# 6-gsm_ctrl.net
KiCad netlist of a schematic drawn in Altium Designer
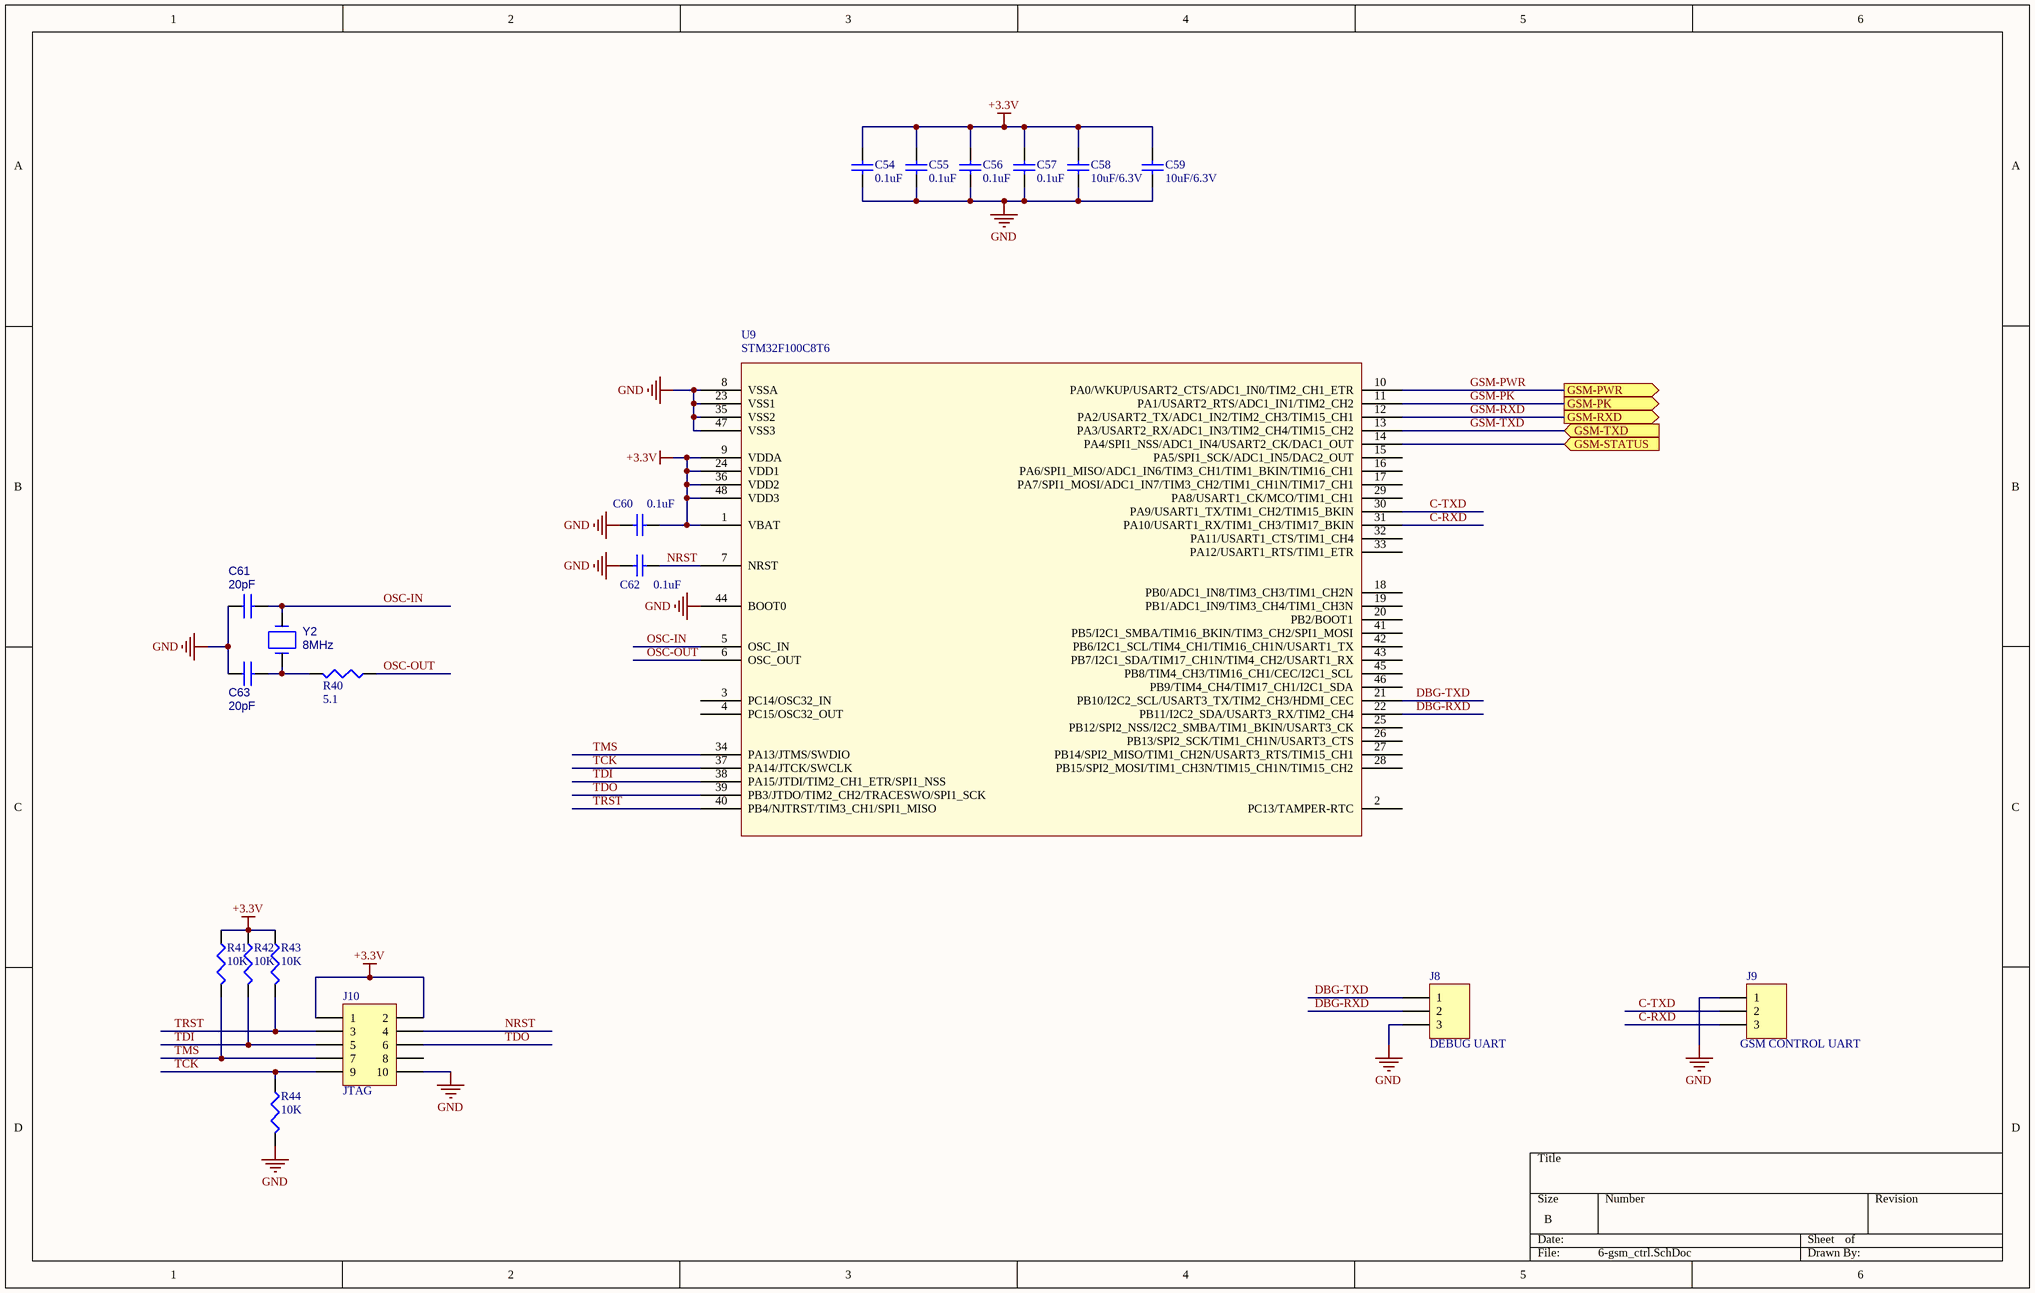
[diagram p0: 6-gsm_ctrl.SchDoc]

(export (version "E")
  (design (tool "Eeschema 10.0.6"))
  (components
    (comp (ref "C54")
      (value "0.1uF")
      (footprint "0603")
      (description "Capacitor")
      (fields (field (name "PUBLISHER") "Altium Limited"))
      (libsource (lib "Miscellaneous Devices") (part "Cap"))
    )
    (comp (ref "C55")
      (value "0.1uF")
      (footprint "0603")
      (description "Capacitor")
      (fields (field (name "PUBLISHER") "Altium Limited"))
      (libsource (lib "Miscellaneous Devices") (part "Cap"))
    )
    (comp (ref "C56")
      (value "0.1uF")
      (footprint "0603")
      (description "Capacitor")
      (fields (field (name "PUBLISHER") "Altium Limited"))
      (libsource (lib "Miscellaneous Devices") (part "Cap"))
    )
    (comp (ref "C57")
      (value "0.1uF")
      (footprint "0603")
      (description "Capacitor")
      (fields (field (name "PUBLISHER") "Altium Limited"))
      (libsource (lib "Miscellaneous Devices") (part "Cap"))
    )
    (comp (ref "C58")
      (value "10uF/6.3V")
      (footprint "0805")
      (description "Capacitor")
      (fields (field (name "PUBLISHER") "Altium Limited"))
      (libsource (lib "Miscellaneous Devices") (part "Cap"))
    )
    (comp (ref "C59")
      (value "10uF/6.3V")
      (footprint "0805")
      (description "Capacitor")
      (fields (field (name "PUBLISHER") "Altium Limited"))
      (libsource (lib "Miscellaneous Devices") (part "Cap"))
    )
    (comp (ref "C60")
      (value "0.1uF")
      (footprint "0603")
      (description "Capacitor")
      (fields (field (name "PUBLISHER") "Altium Limited"))
      (libsource (lib "Miscellaneous Devices") (part "Cap"))
    )
    (comp (ref "C61") (value "20pF") (libsource (lib "*") (part "CAP_Dup1")))
    (comp (ref "C62")
      (value "0.1uF")
      (footprint "0603")
      (description "Capacitor")
      (fields (field (name "PUBLISHER") "Altium Limited"))
      (libsource (lib "Miscellaneous Devices") (part "Cap"))
    )
    (comp (ref "C63") (value "20pF") (libsource (lib "*") (part "CAP_Dup1")))
    (comp (ref "J8")
      (value "DEBUG UART")
      (footprint "HDR1X3")
      (description "Header, 3-Pin")
      (fields (field (name "PUBLISHER") "Altium Limited"))
      (libsource (lib "Miscellaneous Connectors") (part "Header 3"))
    )
    (comp (ref "J9")
      (value "GSM CONTROL UART")
      (footprint "CONN-3P")
      (description "Header, 3-Pin")
      (fields (field (name "PUBLISHER") "Altium Limited"))
      (libsource (lib "Miscellaneous Connectors") (part "Header 3"))
    )
    (comp (ref "J10")
      (value "JTAG")
      (footprint "HDR2X5")
      (description "Header, 5-Pin, Dual row")
      (fields (field (name "PUBLISHER") "Altium Limited"))
      (libsource (lib "Miscellaneous Connectors") (part "Header 5X2"))
    )
    (comp (ref "R40")
      (value "5.1")
      (footprint "0603")
      (description "Resistor")
      (fields (field (name "PUBLISHER") "Altium Limited"))
      (libsource (lib "Miscellaneous Devices") (part "Res3"))
    )
    (comp (ref "R41")
      (value "10K")
      (footprint "0603")
      (description "Resistor")
      (fields (field (name "PUBLISHER") "Altium Limited"))
      (libsource (lib "Miscellaneous Devices") (part "Res3"))
    )
    (comp (ref "R42")
      (value "10K")
      (footprint "0603")
      (description "Resistor")
      (fields (field (name "PUBLISHER") "Altium Limited"))
      (libsource (lib "Miscellaneous Devices") (part "Res3"))
    )
    (comp (ref "R43")
      (value "10K")
      (footprint "0603")
      (description "Resistor")
      (fields (field (name "PUBLISHER") "Altium Limited"))
      (libsource (lib "Miscellaneous Devices") (part "Res3"))
    )
    (comp (ref "R44")
      (value "10K")
      (footprint "0603")
      (description "Resistor")
      (fields (field (name "PUBLISHER") "Altium Limited"))
      (libsource (lib "Miscellaneous Devices") (part "Res3"))
    )
    (comp (ref "U9")
      (value "STM32F100C8T6")
      (footprint "LQFP48")
      (libsource (lib "Schlib") (part "STM32F100XX-LQFP48"))
    )
    (comp (ref "Y2") (value "8MHz") (libsource (lib "*") (part "CRYSTAL")))
  )
  (nets
    (net (code "1") (name "+3.3V") (class "Default")
      (node (ref "C54") (pin "1") (pinfunction "1_1") (pintype "passive"))
      (node (ref "C55") (pin "1") (pinfunction "1_1") (pintype "passive"))
      (node (ref "C56") (pin "1") (pinfunction "1_1") (pintype "passive"))
      (node (ref "C57") (pin "1") (pinfunction "1_1") (pintype "passive"))
      (node (ref "C58") (pin "1") (pinfunction "1_1") (pintype "passive"))
      (node (ref "C59") (pin "1") (pinfunction "1_1") (pintype "passive"))
      (node (ref "C60") (pin "1") (pinfunction "1_1") (pintype "passive"))
      (node (ref "J10") (pin "1") (pinfunction "1_1") (pintype "passive"))
      (node (ref "J10") (pin "2") (pinfunction "2_2") (pintype "passive"))
      (node (ref "R41") (pin "1") (pinfunction "1_1") (pintype "passive"))
      (node (ref "R42") (pin "1") (pinfunction "1_1") (pintype "passive"))
      (node (ref "R43") (pin "1") (pinfunction "1_1") (pintype "passive"))
      (node (ref "U9") (pin "1") (pinfunction "VBAT_1") (pintype "passive"))
      (node (ref "U9") (pin "24") (pinfunction "VDD1_24") (pintype "passive"))
      (node (ref "U9") (pin "36") (pinfunction "VDD2_36") (pintype "passive"))
      (node (ref "U9") (pin "48") (pinfunction "VDD3_48") (pintype "passive"))
      (node (ref "U9") (pin "9") (pinfunction "VDDA_9") (pintype "passive"))
    )
    (net (code "2") (name "/C-RXD") (class "Default")
      (node (ref "J9") (pin "3") (pinfunction "3_3") (pintype "passive"))
      (node (ref "U9") (pin "31") (pinfunction "PA10/USART1_RX/TIM1_CH3/TIM17_BKIN_31") (pintype "passive"))
    )
    (net (code "3") (name "/C-TXD") (class "Default")
      (node (ref "J9") (pin "2") (pinfunction "2_2") (pintype "passive"))
      (node (ref "U9") (pin "30") (pinfunction "PA9/USART1_TX/TIM1_CH2/TIM15_BKIN_30") (pintype "passive"))
    )
    (net (code "4") (name "/DBG-RXD") (class "Default")
      (node (ref "J8") (pin "2") (pinfunction "2_2") (pintype "passive"))
      (node (ref "U9") (pin "22") (pinfunction "PB11/I2C2_SDA/USART3_RX/TIM2_CH4_22") (pintype "passive"))
    )
    (net (code "5") (name "/DBG-TXD") (class "Default")
      (node (ref "J8") (pin "1") (pinfunction "1_1") (pintype "passive"))
      (node (ref "U9") (pin "21") (pinfunction "PB10/I2C2_SCL/USART3_TX/TIM2_CH3/HDMI_CEC_21") (pintype "passive"))
    )
    (net (code "6") (name "/GSM-PK") (class "Default")
      (node (ref "U9") (pin "11") (pinfunction "PA1/USART2_RTS/ADC1_IN1/TIM2_CH2_11") (pintype "passive"))
    )
    (net (code "7") (name "/GSM-PWR") (class "Default")
      (node (ref "U9") (pin "10") (pinfunction "PA0/WKUP/USART2_CTS/ADC1_IN0/TIM2_CH1_ETR_10") (pintype "passive"))
    )
    (net (code "8") (name "/GSM-RXD") (class "Default")
      (node (ref "U9") (pin "12") (pinfunction "PA2/USART2_TX/ADC1_IN2/TIM2_CH3/TIM15_CH1_12") (pintype "passive"))
    )
    (net (code "9") (name "/GSM-STATUS") (class "Default")
      (node (ref "U9") (pin "14") (pinfunction "PA4/SPI1_NSS/ADC1_IN4/USART2_CK/DAC1_OUT_14") (pintype "passive"))
    )
    (net (code "10") (name "/GSM-TXD") (class "Default")
      (node (ref "U9") (pin "13") (pinfunction "PA3/USART2_RX/ADC1_IN3/TIM2_CH4/TIM15_CH2_13") (pintype "passive"))
    )
    (net (code "11") (name "/NRST") (class "Default")
      (node (ref "C62") (pin "2") (pinfunction "2_2") (pintype "passive"))
      (node (ref "J10") (pin "4") (pinfunction "4_4") (pintype "passive"))
      (node (ref "U9") (pin "7") (pinfunction "NRST_7") (pintype "passive"))
    )
    (net (code "12") (name "/OSC-IN") (class "Default")
      (node (ref "C61") (pin "2") (pinfunction "2_2") (pintype "passive"))
      (node (ref "U9") (pin "5") (pinfunction "OSC_IN_5") (pintype "passive"))
      (node (ref "Y2") (pin "2") (pinfunction "2_2") (pintype "passive"))
    )
    (net (code "13") (name "/OSC-OUT") (class "Default")
      (node (ref "R40") (pin "1") (pinfunction "1_1") (pintype "passive"))
      (node (ref "U9") (pin "6") (pinfunction "OSC_OUT_6") (pintype "passive"))
    )
    (net (code "14") (name "/TCK") (class "Default")
      (node (ref "J10") (pin "9") (pinfunction "9_9") (pintype "passive"))
      (node (ref "R44") (pin "1") (pinfunction "1_1") (pintype "passive"))
      (node (ref "U9") (pin "37") (pinfunction "PA14/JTCK/SWCLK_37") (pintype "passive"))
    )
    (net (code "15") (name "/TDI") (class "Default")
      (node (ref "J10") (pin "5") (pinfunction "5_5") (pintype "passive"))
      (node (ref "R42") (pin "2") (pinfunction "2_2") (pintype "passive"))
      (node (ref "U9") (pin "38") (pinfunction "PA15/JTDI/TIM2_CH1_ETR/SPI1_NSS_38") (pintype "passive"))
    )
    (net (code "16") (name "/TDO") (class "Default")
      (node (ref "J10") (pin "6") (pinfunction "6_6") (pintype "passive"))
      (node (ref "U9") (pin "39") (pinfunction "PB3/JTDO/TIM2_CH2/TRACESWO/SPI1_SCK_39") (pintype "passive"))
    )
    (net (code "17") (name "/TMS") (class "Default")
      (node (ref "J10") (pin "7") (pinfunction "7_7") (pintype "passive"))
      (node (ref "R41") (pin "2") (pinfunction "2_2") (pintype "passive"))
      (node (ref "U9") (pin "34") (pinfunction "PA13/JTMS/SWDIO_34") (pintype "passive"))
    )
    (net (code "18") (name "/TRST") (class "Default")
      (node (ref "J10") (pin "3") (pinfunction "3_3") (pintype "passive"))
      (node (ref "R43") (pin "2") (pinfunction "2_2") (pintype "passive"))
      (node (ref "U9") (pin "40") (pinfunction "PB4/NJTRST/TIM3_CH1/SPI1_MISO_40") (pintype "passive"))
    )
    (net (code "19") (name "GND") (class "Default")
      (node (ref "C54") (pin "2") (pinfunction "2_2") (pintype "passive"))
      (node (ref "C55") (pin "2") (pinfunction "2_2") (pintype "passive"))
      (node (ref "C56") (pin "2") (pinfunction "2_2") (pintype "passive"))
      (node (ref "C57") (pin "2") (pinfunction "2_2") (pintype "passive"))
      (node (ref "C58") (pin "2") (pinfunction "2_2") (pintype "passive"))
      (node (ref "C59") (pin "2") (pinfunction "2_2") (pintype "passive"))
      (node (ref "C60") (pin "2") (pinfunction "2_2") (pintype "passive"))
      (node (ref "C61") (pin "1") (pinfunction "1_1") (pintype "passive"))
      (node (ref "C62") (pin "1") (pinfunction "1_1") (pintype "passive"))
      (node (ref "C63") (pin "1") (pinfunction "1_1") (pintype "passive"))
      (node (ref "J10") (pin "10") (pinfunction "10_10") (pintype "passive"))
      (node (ref "J8") (pin "3") (pinfunction "3_3") (pintype "passive"))
      (node (ref "J9") (pin "1") (pinfunction "1_1") (pintype "passive"))
      (node (ref "R44") (pin "2") (pinfunction "2_2") (pintype "passive"))
      (node (ref "U9") (pin "23") (pinfunction "VSS1_23") (pintype "passive"))
      (node (ref "U9") (pin "35") (pinfunction "VSS2_35") (pintype "passive"))
      (node (ref "U9") (pin "44") (pinfunction "BOOT0_44") (pintype "passive"))
      (node (ref "U9") (pin "47") (pinfunction "VSS3_47") (pintype "passive"))
      (node (ref "U9") (pin "8") (pinfunction "VSSA_8") (pintype "passive"))
    )
    (net (code "20") (name "Net-(C63-Pad2)") (class "Default")
      (node (ref "C63") (pin "2") (pinfunction "2_2") (pintype "passive"))
      (node (ref "R40") (pin "2") (pinfunction "2_2") (pintype "passive"))
      (node (ref "Y2") (pin "1") (pinfunction "1_1") (pintype "passive"))
    )
    (net (code "21") (name "unconnected-(J10-Pad8)") (class "Default")
      (node (ref "J10") (pin "8") (pinfunction "8_8") (pintype "passive"))
    )
    (net (code "22") (name "unconnected-(U9-PA5{slash}SPI1_SCK{slash}ADC1_IN5{slash}DAC2_OUT-Pad15)") (class "Default")
      (node (ref "U9") (pin "15") (pinfunction "PA5/SPI1_SCK/ADC1_IN5/DAC2_OUT_15") (pintype "passive"))
    )
    (net (code "23") (name "unconnected-(U9-PA6{slash}SPI1_MISO{slash}ADC1_IN6{slash}TIM3_CH1{slash}TIM1_BKIN{slash}TIM16_CH1-Pad16)") (class "Default")
      (node (ref "U9") (pin "16") (pinfunction "PA6/SPI1_MISO/ADC1_IN6/TIM3_CH1/TIM1_BKIN/TIM16_CH1_16") (pintype "passive"))
    )
    (net (code "24") (name "unconnected-(U9-PA7{slash}SPI1_MOSI{slash}ADC1_IN7{slash}TIM3_CH2{slash}TIM1_CH1N{slash}TIM17_CH1-Pad17)") (class "Default")
      (node (ref "U9") (pin "17") (pinfunction "PA7/SPI1_MOSI/ADC1_IN7/TIM3_CH2/TIM1_CH1N/TIM17_CH1_17") (pintype "passive"))
    )
    (net (code "25") (name "unconnected-(U9-PA8{slash}USART1_CK{slash}MCO{slash}TIM1_CH1-Pad29)") (class "Default")
      (node (ref "U9") (pin "29") (pinfunction "PA8/USART1_CK/MCO/TIM1_CH1_29") (pintype "passive"))
    )
    (net (code "26") (name "unconnected-(U9-PA11{slash}USART1_CTS{slash}TIM1_CH4-Pad32)") (class "Default")
      (node (ref "U9") (pin "32") (pinfunction "PA11/USART1_CTS/TIM1_CH4_32") (pintype "passive"))
    )
    (net (code "27") (name "unconnected-(U9-PA12{slash}USART1_RTS{slash}TIM1_ETR-Pad33)") (class "Default")
      (node (ref "U9") (pin "33") (pinfunction "PA12/USART1_RTS/TIM1_ETR_33") (pintype "passive"))
    )
    (net (code "28") (name "unconnected-(U9-PB0{slash}ADC1_IN8{slash}TIM3_CH3{slash}TIM1_CH2N-Pad18)") (class "Default")
      (node (ref "U9") (pin "18") (pinfunction "PB0/ADC1_IN8/TIM3_CH3/TIM1_CH2N_18") (pintype "passive"))
    )
    (net (code "29") (name "unconnected-(U9-PB1{slash}ADC1_IN9{slash}TIM3_CH4{slash}TIM1_CH3N-Pad19)") (class "Default")
      (node (ref "U9") (pin "19") (pinfunction "PB1/ADC1_IN9/TIM3_CH4/TIM1_CH3N_19") (pintype "passive"))
    )
    (net (code "30") (name "unconnected-(U9-PB2{slash}BOOT1-Pad20)") (class "Default")
      (node (ref "U9") (pin "20") (pinfunction "PB2/BOOT1_20") (pintype "passive"))
    )
    (net (code "31") (name "unconnected-(U9-PB5{slash}I2C1_SMBA{slash}TIM16_BKIN{slash}TIM3_CH2{slash}SPI1_MOSI-Pad41)") (class "Default")
      (node (ref "U9") (pin "41") (pinfunction "PB5/I2C1_SMBA/TIM16_BKIN/TIM3_CH2/SPI1_MOSI_41") (pintype "passive"))
    )
    (net (code "32") (name "unconnected-(U9-PB6{slash}I2C1_SCL{slash}TIM4_CH1{slash}TIM16_CH1N{slash}USART1_TX-Pad42)") (class "Default")
      (node (ref "U9") (pin "42") (pinfunction "PB6/I2C1_SCL/TIM4_CH1/TIM16_CH1N/USART1_TX_42") (pintype "passive"))
    )
    (net (code "33") (name "unconnected-(U9-PB7{slash}I2C1_SDA{slash}TIM17_CH1N{slash}TIM4_CH2{slash}USART1_RX-Pad43)") (class "Default")
      (node (ref "U9") (pin "43") (pinfunction "PB7/I2C1_SDA/TIM17_CH1N/TIM4_CH2/USART1_RX_43") (pintype "passive"))
    )
    (net (code "34") (name "unconnected-(U9-PB8{slash}TIM4_CH3{slash}TIM16_CH1{slash}CEC{slash}I2C1_SCL-Pad45)") (class "Default")
      (node (ref "U9") (pin "45") (pinfunction "PB8/TIM4_CH3/TIM16_CH1/CEC/I2C1_SCL_45") (pintype "passive"))
    )
    (net (code "35") (name "unconnected-(U9-PB9{slash}TIM4_CH4{slash}TIM17_CH1{slash}I2C1_SDA-Pad46)") (class "Default")
      (node (ref "U9") (pin "46") (pinfunction "PB9/TIM4_CH4/TIM17_CH1/I2C1_SDA_46") (pintype "passive"))
    )
    (net (code "36") (name "unconnected-(U9-PB12{slash}SPI2_NSS{slash}I2C2_SMBA{slash}TIM1_BKIN{slash}USART3_CK-Pad25)") (class "Default")
      (node (ref "U9") (pin "25") (pinfunction "PB12/SPI2_NSS/I2C2_SMBA/TIM1_BKIN/USART3_CK_25") (pintype "passive"))
    )
    (net (code "37") (name "unconnected-(U9-PB13{slash}SPI2_SCK{slash}TIM1_CH1N{slash}USART3_CTS-Pad26)") (class "Default")
      (node (ref "U9") (pin "26") (pinfunction "PB13/SPI2_SCK/TIM1_CH1N/USART3_CTS_26") (pintype "passive"))
    )
    (net (code "38") (name "unconnected-(U9-PB14{slash}SPI2_MISO{slash}TIM1_CH2N{slash}USART3_RTS{slash}TIM15_CH1-Pad27)") (class "Default")
      (node (ref "U9") (pin "27") (pinfunction "PB14/SPI2_MISO/TIM1_CH2N/USART3_RTS/TIM15_CH1_27") (pintype "passive"))
    )
    (net (code "39") (name "unconnected-(U9-PB15{slash}SPI2_MOSI{slash}TIM1_CH3N{slash}TIM15_CH1N{slash}TIM15_CH2-Pad28)") (class "Default")
      (node (ref "U9") (pin "28") (pinfunction "PB15/SPI2_MOSI/TIM1_CH3N/TIM15_CH1N/TIM15_CH2_28") (pintype "passive"))
    )
    (net (code "40") (name "unconnected-(U9-PC13{slash}TAMPER-RTC-Pad2)") (class "Default")
      (node (ref "U9") (pin "2") (pinfunction "PC13/TAMPER-RTC_2") (pintype "passive"))
    )
    (net (code "41") (name "unconnected-(U9-PC14{slash}OSC32_IN-Pad3)") (class "Default")
      (node (ref "U9") (pin "3") (pinfunction "PC14/OSC32_IN_3") (pintype "passive"))
    )
    (net (code "42") (name "unconnected-(U9-PC15{slash}OSC32_OUT-Pad4)") (class "Default")
      (node (ref "U9") (pin "4") (pinfunction "PC15/OSC32_OUT_4") (pintype "passive"))
    )
  )
)
